# 12vRelayDriver.net
KiCad netlist of a schematic drawn in EAGLE
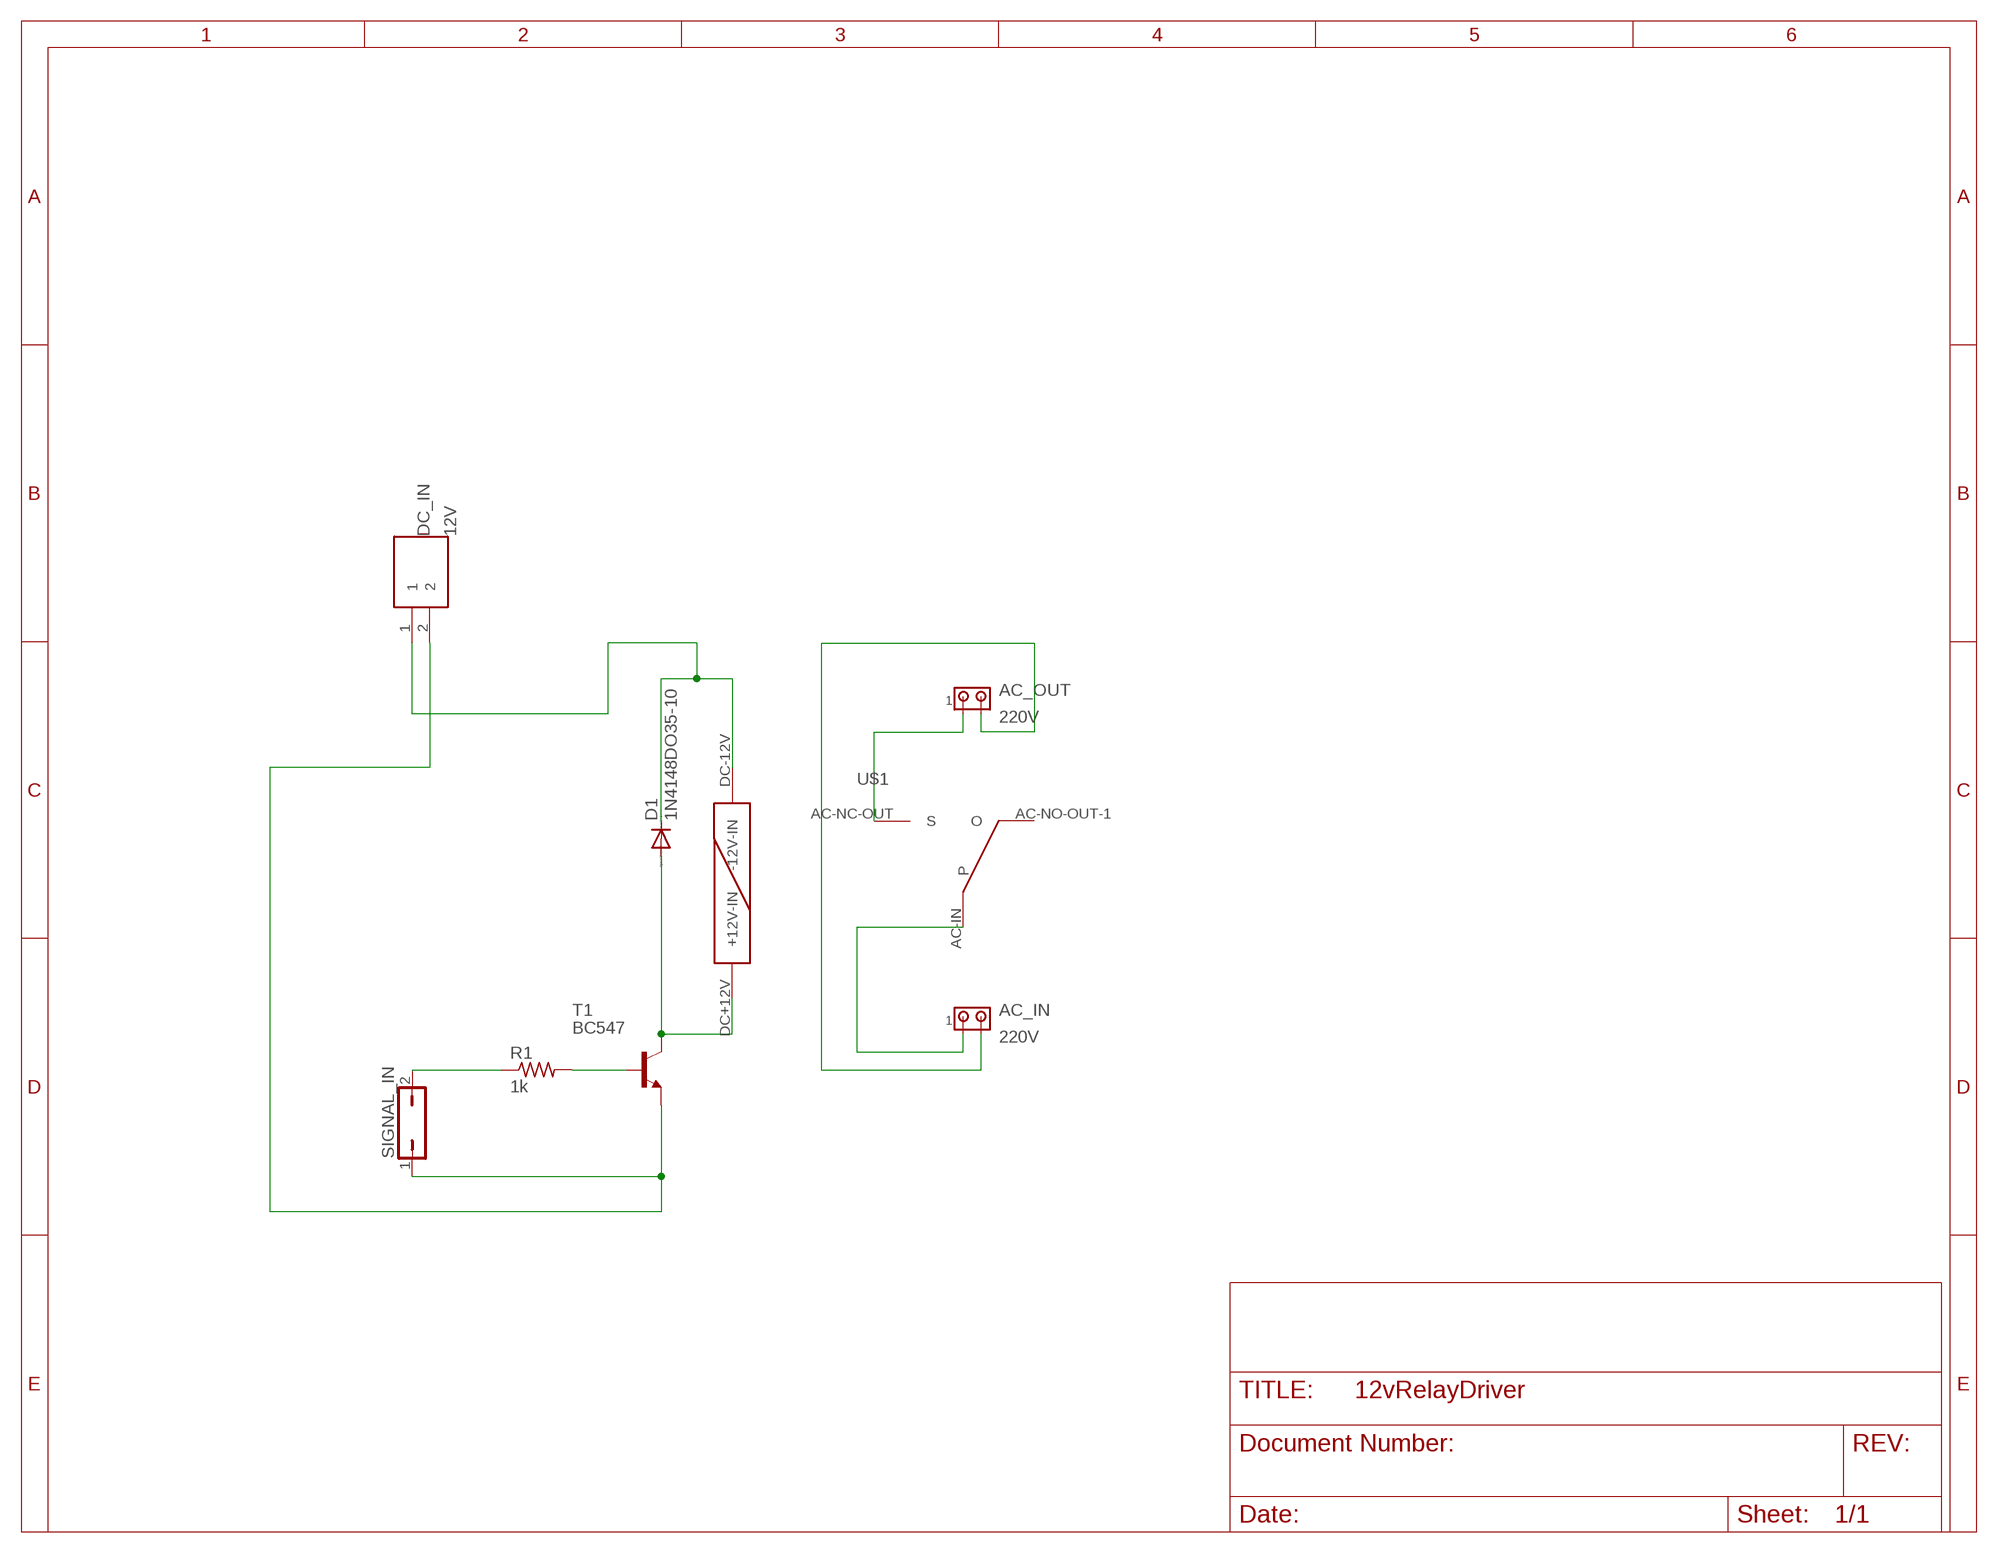
[diagram p0: schematic, sheet 1]

(export (version "E")
  (design (tool "Eeschema 10.0.6"))
  (components
    (comp (ref "AC_IN")
      (value "220V")
      (footprint "eagle-import:1X2MTA")
      (libsource (lib "eagle-import") (part "MTA02-156"))
    )
    (comp (ref "AC_OUT")
      (value "220V")
      (footprint "eagle-import:1X2MTA")
      (libsource (lib "eagle-import") (part "MTA02-156"))
    )
    (comp (ref "D1")
      (value "1N4148DO35-10")
      (footprint "eagle-import:DO35-10")
      (libsource (lib "eagle-import") (part "1N4148DO35-10"))
    )
    (comp (ref "DC_IN")
      (value "12V")
      (footprint "eagle-import:TE_440055-2")
      (fields (field (name "COMMENT") "440055-2") (field (name "MF") "TE Connectivity"))
      (libsource (lib "eagle-import") (part "440055-2"))
    )
    (comp (ref "R1")
      (value "1k")
      (footprint "eagle-import:0204_7")
      (libsource (lib "eagle-import") (part "R-US_0204/7"))
    )
    (comp (ref "SIGNAL_IN")
      (value "JP1Q")
      (footprint "eagle-import:JP1")
      (libsource (lib "eagle-import") (part "JP1Q"))
    )
    (comp (ref "T1")
      (value "BC547")
      (footprint "eagle-import:TO92")
      (fields (field (name "MF") "Fairchild Semiconductor"))
      (libsource (lib "eagle-import") (part "BC547"))
    )
    (comp (ref "U$1")
      (value "GU-D-2-6")
      (footprint "eagle-import:GU-D-2-6")
      (libsource (lib "eagle-import") (part "GU-D-2-6"))
    )
  )
  (nets
    (net (code "1") (name "Net-(AC_IN-Pad2)") (class "Default")
      (node (ref "AC_IN") (pin "2") (pinfunction "2_2") (pintype "passive"))
      (node (ref "AC_OUT") (pin "2") (pinfunction "2_2") (pintype "passive"))
    )
    (net (code "2") (name "Net-(R1-Pad1)") (class "Default")
      (node (ref "R1") (pin "1") (pinfunction "1_1") (pintype "passive"))
      (node (ref "SIGNAL_IN") (pin "2") (pinfunction "2_2") (pintype "passive"))
    )
    (net (code "3") (name "Net-(T1-B)") (class "Default")
      (node (ref "R1") (pin "2") (pinfunction "2_2") (pintype "passive"))
      (node (ref "T1") (pin "2") (pinfunction "B_2") (pintype "passive"))
    )
    (net (code "4") (name "Net-(T1-C)") (class "Default")
      (node (ref "D1") (pin "A") (pinfunction "A_A") (pintype "passive"))
      (node (ref "T1") (pin "3") (pinfunction "C_3") (pintype "passive"))
      (node (ref "U$1") (pin "DC+12V") (pinfunction "+12V-IN_DC+12V") (pintype "passive"))
    )
    (net (code "5") (name "Net-(T1-E)") (class "Default")
      (node (ref "DC_IN") (pin "2") (pinfunction "2_2") (pintype "passive"))
      (node (ref "SIGNAL_IN") (pin "1") (pinfunction "1_1") (pintype "passive"))
      (node (ref "T1") (pin "1") (pinfunction "E_1") (pintype "passive"))
    )
    (net (code "6") (name "Net-(U$1--12V-IN)") (class "Default")
      (node (ref "D1") (pin "C") (pinfunction "C_C") (pintype "passive"))
      (node (ref "DC_IN") (pin "1") (pinfunction "1_1") (pintype "passive"))
      (node (ref "U$1") (pin "DC-12V") (pinfunction "-12V-IN_DC-12V") (pintype "passive"))
    )
    (net (code "7") (name "Net-(U$1-P)") (class "Default")
      (node (ref "AC_IN") (pin "1") (pinfunction "1_1") (pintype "passive"))
      (node (ref "U$1") (pin "AC-IN") (pinfunction "P_AC-IN") (pintype "passive"))
    )
    (net (code "8") (name "Net-(U$1-S)") (class "Default")
      (node (ref "AC_OUT") (pin "1") (pinfunction "1_1") (pintype "passive"))
      (node (ref "U$1") (pin "AC-NC-OUT") (pinfunction "S_AC-NC-OUT") (pintype "passive"))
    )
    (net (code "9") (name "unconnected-(U$1-O-PadAC-NO-OUT-1)") (class "Default")
      (node (ref "U$1") (pin "AC-NO-OUT-1") (pinfunction "O_AC-NO-OUT-1") (pintype "passive"))
    )
  )
)
